# Underwater_ROV_Sensors.net
KiCad netlist of a schematic drawn in Altium Designer
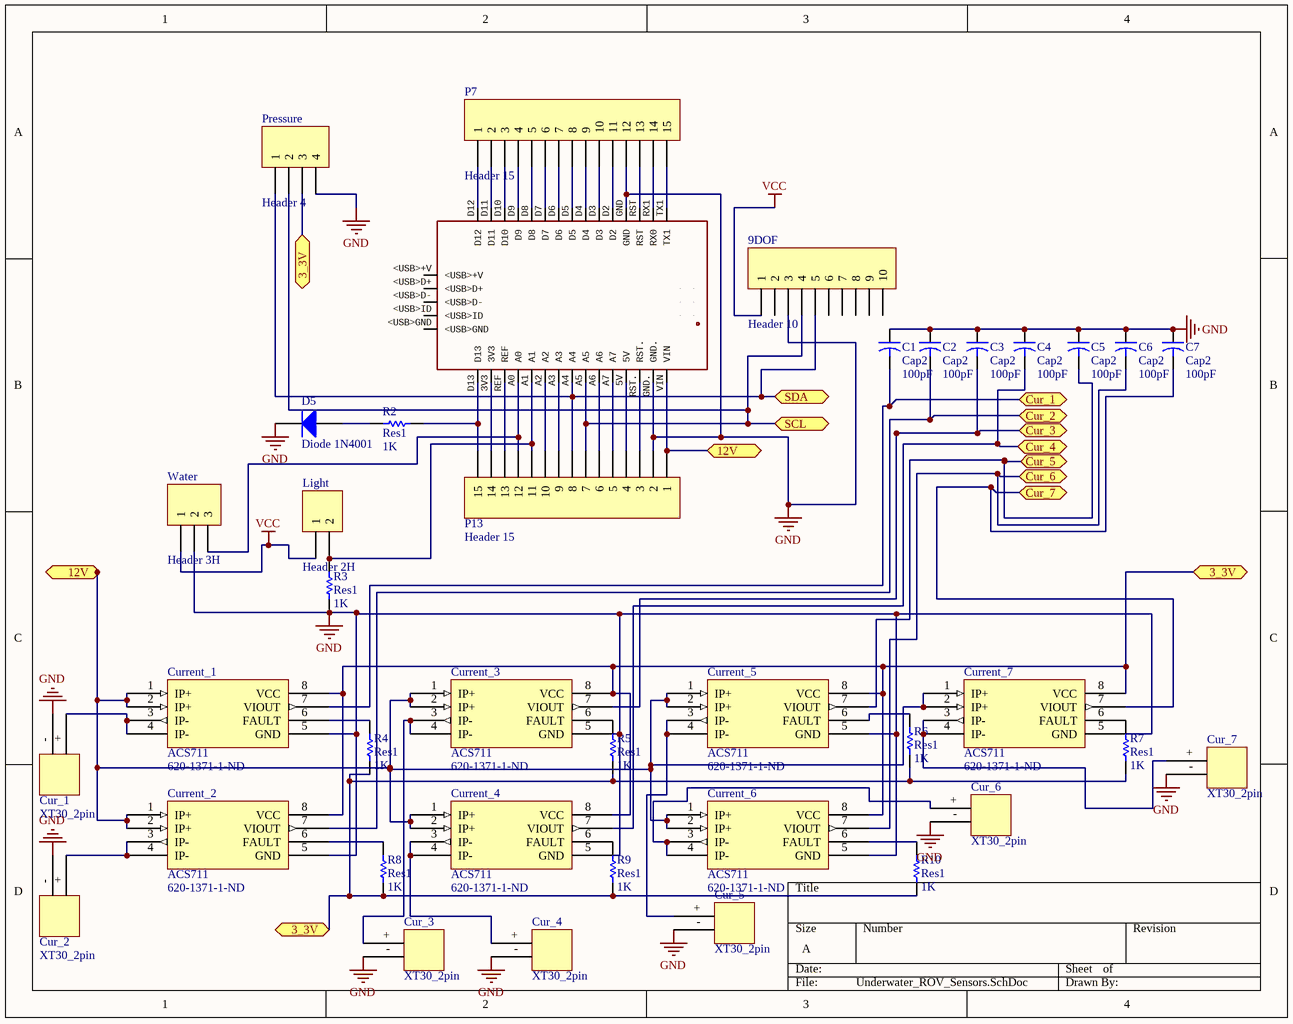
[diagram p0: Underwater_ROV_Sensors.SchDoc]

(export (version "E")
  (design (tool "Eeschema 10.0.6"))
  (components
    (comp (ref "9DOF")
      (value "Header 10")
      (footprint "HDR1X10")
      (description "Header, 10-Pin")
      (fields (field (name "PUBLISHER") "Altium Limited"))
      (libsource (lib "Miscellaneous Connectors") (part "Header 10"))
    )
    (comp (ref "C1")
      (value "Cap2")
      (footprint "CAPR5-4X5")
      (description "Capacitor")
      (fields (field (name "ALTIUM_VALUE") "100pF") (field (name "PUBLISHER") "Altium Limited"))
      (libsource (lib "Miscellaneous Devices") (part "Cap2"))
    )
    (comp (ref "C2")
      (value "Cap2")
      (footprint "CAPR5-4X5")
      (description "Capacitor")
      (fields (field (name "ALTIUM_VALUE") "100pF") (field (name "PUBLISHER") "Altium Limited"))
      (libsource (lib "Miscellaneous Devices") (part "Cap2"))
    )
    (comp (ref "C3")
      (value "Cap2")
      (footprint "CAPR5-4X5")
      (description "Capacitor")
      (fields (field (name "ALTIUM_VALUE") "100pF") (field (name "PUBLISHER") "Altium Limited"))
      (libsource (lib "Miscellaneous Devices") (part "Cap2"))
    )
    (comp (ref "C4")
      (value "Cap2")
      (footprint "CAPR5-4X5")
      (description "Capacitor")
      (fields (field (name "ALTIUM_VALUE") "100pF") (field (name "PUBLISHER") "Altium Limited"))
      (libsource (lib "Miscellaneous Devices") (part "Cap2"))
    )
    (comp (ref "C5")
      (value "Cap2")
      (footprint "CAPR5-4X5")
      (description "Capacitor")
      (fields (field (name "ALTIUM_VALUE") "100pF") (field (name "PUBLISHER") "Altium Limited"))
      (libsource (lib "Miscellaneous Devices") (part "Cap2"))
    )
    (comp (ref "C6")
      (value "Cap2")
      (footprint "CAPR5-4X5")
      (description "Capacitor")
      (fields (field (name "ALTIUM_VALUE") "100pF") (field (name "PUBLISHER") "Altium Limited"))
      (libsource (lib "Miscellaneous Devices") (part "Cap2"))
    )
    (comp (ref "C7")
      (value "Cap2")
      (footprint "CAPR5-4X5")
      (description "Capacitor")
      (fields (field (name "ALTIUM_VALUE") "100pF") (field (name "PUBLISHER") "Altium Limited"))
      (libsource (lib "Miscellaneous Devices") (part "Cap2"))
    )
    (comp (ref "Current_1")
      (value "ACS711")
      (footprint "SOIC127P600X175-8N")
      (fields
        (field (name "MANUFACTURER") "Allegro MicroSystems, LLC")
        (field (name "MANUFACTURER PART NUMBER") "ACS711ELCTR-25AB-T")
        (field (name "SUPPLIER PART NUMBER 1") "620-1371-1-ND")
      )
      (libsource (lib "UROV_Aux_Lib") (part "ACS711"))
    )
    (comp (ref "Current_2")
      (value "ACS711")
      (footprint "SOIC127P600X175-8N")
      (fields
        (field (name "MANUFACTURER") "Allegro MicroSystems, LLC")
        (field (name "MANUFACTURER PART NUMBER") "ACS711ELCTR-25AB-T")
        (field (name "SUPPLIER PART NUMBER 1") "620-1371-1-ND")
      )
      (libsource (lib "UROV_Aux_Lib") (part "ACS711"))
    )
    (comp (ref "Current_3")
      (value "ACS711")
      (footprint "SOIC127P600X175-8N")
      (fields
        (field (name "MANUFACTURER") "Allegro MicroSystems, LLC")
        (field (name "MANUFACTURER PART NUMBER") "ACS711ELCTR-25AB-T")
        (field (name "SUPPLIER PART NUMBER 1") "620-1371-1-ND")
      )
      (libsource (lib "UROV_Aux_Lib") (part "ACS711"))
    )
    (comp (ref "Current_4")
      (value "ACS711")
      (footprint "SOIC127P600X175-8N")
      (fields
        (field (name "MANUFACTURER") "Allegro MicroSystems, LLC")
        (field (name "MANUFACTURER PART NUMBER") "ACS711ELCTR-25AB-T")
        (field (name "SUPPLIER PART NUMBER 1") "620-1371-1-ND")
      )
      (libsource (lib "UROV_Aux_Lib") (part "ACS711"))
    )
    (comp (ref "Current_5")
      (value "ACS711")
      (footprint "SOIC127P600X175-8N")
      (fields
        (field (name "MANUFACTURER") "Allegro MicroSystems, LLC")
        (field (name "MANUFACTURER PART NUMBER") "ACS711ELCTR-25AB-T")
        (field (name "SUPPLIER PART NUMBER 1") "620-1371-1-ND")
      )
      (libsource (lib "UROV_Aux_Lib") (part "ACS711"))
    )
    (comp (ref "Current_6")
      (value "ACS711")
      (footprint "SOIC127P600X175-8N")
      (fields
        (field (name "MANUFACTURER") "Allegro MicroSystems, LLC")
        (field (name "MANUFACTURER PART NUMBER") "ACS711ELCTR-25AB-T")
        (field (name "SUPPLIER PART NUMBER 1") "620-1371-1-ND")
      )
      (libsource (lib "UROV_Aux_Lib") (part "ACS711"))
    )
    (comp (ref "Current_7")
      (value "ACS711")
      (footprint "SOIC127P600X175-8N")
      (fields
        (field (name "MANUFACTURER") "Allegro MicroSystems, LLC")
        (field (name "MANUFACTURER PART NUMBER") "ACS711ELCTR-25AB-T")
        (field (name "SUPPLIER PART NUMBER 1") "620-1371-1-ND")
      )
      (libsource (lib "UROV_Aux_Lib") (part "ACS711"))
    )
    (comp (ref "Cur_1")
      (value "XT30_2pin")
      (footprint "XT30_2pin")
      (libsource (lib "UROV_Aux_Lib") (part "XT30_2pin"))
    )
    (comp (ref "Cur_2")
      (value "XT30_2pin")
      (footprint "XT30_2pin")
      (libsource (lib "UROV_Aux_Lib") (part "XT30_2pin"))
    )
    (comp (ref "Cur_3") (value "XT30_2pin") (footprint "XT30_2pin") (libsource (lib "") (part "XT30_2pin_1")))
    (comp (ref "Cur_4") (value "XT30_2pin") (footprint "XT30_2pin") (libsource (lib "") (part "XT30_2pin_1")))
    (comp (ref "Cur_5") (value "XT30_2pin") (footprint "XT30_2pin") (libsource (lib "") (part "XT30_2pin_1")))
    (comp (ref "Cur_6") (value "XT30_2pin") (footprint "XT30_2pin") (libsource (lib "") (part "XT30_2pin_1")))
    (comp (ref "Cur_7") (value "XT30_2pin") (footprint "XT30_2pin") (libsource (lib "") (part "XT30_2pin_1")))
    (comp (ref "D5")
      (value "Diode 1N4001")
      (footprint "DO-41")
      (description "1 Amp General Purpose Rectifier")
      (fields (field (name "PUBLISHER") "Altium Limited"))
      (libsource (lib "Miscellaneous Devices") (part "Diode 1N4001"))
    )
    (comp (ref "Light")
      (value "Header 2H")
      (footprint "HDR1X2H")
      (description "Header, 2-Pin, Right Angle")
      (fields (field (name "PUBLISHER") "Altium Limited"))
      (libsource (lib "Miscellaneous Connectors") (part "Header 2H"))
    )
    (comp (ref "Nano_sens")
      (value "Device for representing an Arduino Nano board with a footprint in an EAGLE design. Created by Dave Young for Element14. More EAGLE documentation at: http://www.element14.com/community/community/knode/cadsoft_eagle")
      (footprint "ARDUINO_NANO")
      (libsource (lib "E14_Arduino_revC") (part "ARDUINO_NANO"))
    )
    (comp (ref "P7")
      (value "Header 15")
      (footprint "HDR1X15")
      (description "Header, 15-Pin")
      (fields (field (name "PUBLISHER") "Altium Limited"))
      (libsource (lib "") (part "Header 15_1"))
    )
    (comp (ref "P13")
      (value "Header 15")
      (footprint "HDR1X15")
      (description "Header, 15-Pin")
      (fields (field (name "PUBLISHER") "Altium Limited"))
      (libsource (lib "Miscellaneous Connectors") (part "Header 15"))
    )
    (comp (ref "Pressure")
      (value "Header 4")
      (footprint "HDR1X4")
      (description "Header, 4-Pin")
      (fields (field (name "PUBLISHER") "Altium Limited"))
      (libsource (lib "Miscellaneous Connectors") (part "Header 4"))
    )
    (comp (ref "R2")
      (value "Res1")
      (footprint "AXIAL-0.3")
      (description "Resistor")
      (fields (field (name "ALTIUM_VALUE") "1K") (field (name "PUBLISHER") "Altium Limited"))
      (libsource (lib "Miscellaneous Devices") (part "Res1"))
    )
    (comp (ref "R3")
      (value "Res1")
      (footprint "AXIAL-0.3")
      (description "Resistor")
      (fields (field (name "ALTIUM_VALUE") "1K") (field (name "PUBLISHER") "Altium Limited"))
      (libsource (lib "Miscellaneous Devices") (part "Res1"))
    )
    (comp (ref "R4")
      (value "Res1")
      (footprint "AXIAL-0.3")
      (description "Resistor")
      (fields (field (name "ALTIUM_VALUE") "1K") (field (name "PUBLISHER") "Altium Limited"))
      (libsource (lib "Miscellaneous Devices") (part "Res1"))
    )
    (comp (ref "R5")
      (value "Res1")
      (footprint "AXIAL-0.3")
      (description "Resistor")
      (fields (field (name "ALTIUM_VALUE") "1K") (field (name "PUBLISHER") "Altium Limited"))
      (libsource (lib "Miscellaneous Devices") (part "Res1"))
    )
    (comp (ref "R6")
      (value "Res1")
      (footprint "AXIAL-0.3")
      (description "Resistor")
      (fields (field (name "ALTIUM_VALUE") "1K") (field (name "PUBLISHER") "Altium Limited"))
      (libsource (lib "Miscellaneous Devices") (part "Res1"))
    )
    (comp (ref "R7")
      (value "Res1")
      (footprint "AXIAL-0.3")
      (description "Resistor")
      (fields (field (name "ALTIUM_VALUE") "1K") (field (name "PUBLISHER") "Altium Limited"))
      (libsource (lib "Miscellaneous Devices") (part "Res1"))
    )
    (comp (ref "R8")
      (value "Res1")
      (footprint "AXIAL-0.3")
      (description "Resistor")
      (fields (field (name "ALTIUM_VALUE") "1K") (field (name "PUBLISHER") "Altium Limited"))
      (libsource (lib "Miscellaneous Devices") (part "Res1"))
    )
    (comp (ref "R9")
      (value "Res1")
      (footprint "AXIAL-0.3")
      (description "Resistor")
      (fields (field (name "ALTIUM_VALUE") "1K") (field (name "PUBLISHER") "Altium Limited"))
      (libsource (lib "Miscellaneous Devices") (part "Res1"))
    )
    (comp (ref "R10")
      (value "Res1")
      (footprint "AXIAL-0.3")
      (description "Resistor")
      (fields (field (name "ALTIUM_VALUE") "1K") (field (name "PUBLISHER") "Altium Limited"))
      (libsource (lib "Miscellaneous Devices") (part "Res1"))
    )
    (comp (ref "Water")
      (value "Header 3H")
      (footprint "HDR1X3H")
      (description "Header, 3-Pin, Right Angle")
      (fields (field (name "PUBLISHER") "Altium Limited"))
      (libsource (lib "Miscellaneous Connectors") (part "Header 3H"))
    )
  )
  (nets
    (net (code "1") (name "/3_3V") (class "Default")
      (node (ref "Current_1") (pin "8") (pinfunction "VCC_8") (pintype "power_in"))
      (node (ref "Current_2") (pin "8") (pinfunction "VCC_8") (pintype "power_in"))
      (node (ref "Current_3") (pin "8") (pinfunction "VCC_8") (pintype "power_in"))
      (node (ref "Current_4") (pin "8") (pinfunction "VCC_8") (pintype "power_in"))
      (node (ref "Current_5") (pin "8") (pinfunction "VCC_8") (pintype "power_in"))
      (node (ref "Current_6") (pin "8") (pinfunction "VCC_8") (pintype "power_in"))
      (node (ref "Current_7") (pin "8") (pinfunction "VCC_8") (pintype "power_in"))
      (node (ref "Pressure") (pin "3") (pinfunction "3_3") (pintype "passive"))
      (node (ref "R10") (pin "1") (pinfunction "1_1") (pintype "passive"))
      (node (ref "R4") (pin "1") (pinfunction "1_1") (pintype "passive"))
      (node (ref "R5") (pin "1") (pinfunction "1_1") (pintype "passive"))
      (node (ref "R6") (pin "1") (pinfunction "1_1") (pintype "passive"))
      (node (ref "R7") (pin "1") (pinfunction "1_1") (pintype "passive"))
      (node (ref "R8") (pin "1") (pinfunction "1_1") (pintype "passive"))
      (node (ref "R9") (pin "1") (pinfunction "1_1") (pintype "passive"))
    )
    (net (code "2") (name "/12V") (class "Default")
      (node (ref "Current_1") (pin "1") (pinfunction "IP+_1") (pintype "input"))
      (node (ref "Current_1") (pin "2") (pinfunction "IP+_2") (pintype "input"))
      (node (ref "Current_2") (pin "1") (pinfunction "IP+_1") (pintype "input"))
      (node (ref "Current_2") (pin "2") (pinfunction "IP+_2") (pintype "input"))
      (node (ref "Current_3") (pin "1") (pinfunction "IP+_1") (pintype "input"))
      (node (ref "Current_3") (pin "2") (pinfunction "IP+_2") (pintype "input"))
      (node (ref "Current_4") (pin "1") (pinfunction "IP+_1") (pintype "input"))
      (node (ref "Current_4") (pin "2") (pinfunction "IP+_2") (pintype "input"))
      (node (ref "Current_5") (pin "1") (pinfunction "IP+_1") (pintype "input"))
      (node (ref "Current_5") (pin "2") (pinfunction "IP+_2") (pintype "input"))
      (node (ref "Current_6") (pin "1") (pinfunction "IP+_1") (pintype "input"))
      (node (ref "Current_6") (pin "2") (pinfunction "IP+_2") (pintype "input"))
      (node (ref "Current_7") (pin "1") (pinfunction "IP+_1") (pintype "input"))
      (node (ref "Current_7") (pin "2") (pinfunction "IP+_2") (pintype "input"))
      (node (ref "Nano_sens") (pin "VIN") (pinfunction "VIN_VIN") (pintype "passive"))
      (node (ref "P13") (pin "1") (pinfunction "1_1") (pintype "passive"))
    )
    (net (code "3") (name "/Cur_1") (class "Default")
      (node (ref "C1") (pin "2") (pinfunction "2_2") (pintype "passive"))
      (node (ref "Current_1") (pin "7") (pinfunction "VIOUT_7") (pintype "output"))
    )
    (net (code "4") (name "/Cur_2") (class "Default")
      (node (ref "C2") (pin "2") (pinfunction "2_2") (pintype "passive"))
      (node (ref "Current_2") (pin "7") (pinfunction "VIOUT_7") (pintype "output"))
    )
    (net (code "5") (name "/Cur_3") (class "Default")
      (node (ref "C3") (pin "2") (pinfunction "2_2") (pintype "passive"))
      (node (ref "Current_3") (pin "7") (pinfunction "VIOUT_7") (pintype "output"))
    )
    (net (code "6") (name "/Cur_4") (class "Default")
      (node (ref "C4") (pin "2") (pinfunction "2_2") (pintype "passive"))
      (node (ref "Current_4") (pin "7") (pinfunction "VIOUT_7") (pintype "output"))
    )
    (net (code "7") (name "/Cur_5") (class "Default")
      (node (ref "C5") (pin "2") (pinfunction "2_2") (pintype "passive"))
      (node (ref "Current_5") (pin "7") (pinfunction "VIOUT_7") (pintype "output"))
    )
    (net (code "8") (name "/Cur_6") (class "Default")
      (node (ref "C6") (pin "2") (pinfunction "2_2") (pintype "passive"))
      (node (ref "Current_6") (pin "7") (pinfunction "VIOUT_7") (pintype "output"))
    )
    (net (code "9") (name "/Cur_7") (class "Default")
      (node (ref "C7") (pin "2") (pinfunction "2_2") (pintype "passive"))
      (node (ref "Current_7") (pin "7") (pinfunction "VIOUT_7") (pintype "output"))
    )
    (net (code "10") (name "/SCL") (class "Default")
      (node (ref "9DOF") (pin "4") (pinfunction "4_4") (pintype "passive"))
      (node (ref "Nano_sens") (pin "A5") (pinfunction "A5_A5") (pintype "passive"))
      (node (ref "P13") (pin "7") (pinfunction "7_7") (pintype "passive"))
      (node (ref "Pressure") (pin "2") (pinfunction "2_2") (pintype "passive"))
    )
    (net (code "11") (name "/SDA") (class "Default")
      (node (ref "9DOF") (pin "5") (pinfunction "5_5") (pintype "passive"))
      (node (ref "Nano_sens") (pin "A4") (pinfunction "A4_A4") (pintype "passive"))
      (node (ref "P13") (pin "8") (pinfunction "8_8") (pintype "passive"))
      (node (ref "Pressure") (pin "1") (pinfunction "1_1") (pintype "passive"))
    )
    (net (code "12") (name "GND") (class "Default")
      (node (ref "9DOF") (pin "3") (pinfunction "3_3") (pintype "passive"))
      (node (ref "C1") (pin "1") (pinfunction "1_1") (pintype "passive"))
      (node (ref "C2") (pin "1") (pinfunction "1_1") (pintype "passive"))
      (node (ref "C3") (pin "1") (pinfunction "1_1") (pintype "passive"))
      (node (ref "C4") (pin "1") (pinfunction "1_1") (pintype "passive"))
      (node (ref "C5") (pin "1") (pinfunction "1_1") (pintype "passive"))
      (node (ref "C6") (pin "1") (pinfunction "1_1") (pintype "passive"))
      (node (ref "C7") (pin "1") (pinfunction "1_1") (pintype "passive"))
      (node (ref "Cur_1") (pin "-") (pintype "passive"))
      (node (ref "Cur_2") (pin "-") (pintype "passive"))
      (node (ref "Cur_3") (pin "-") (pintype "passive"))
      (node (ref "Cur_4") (pin "-") (pintype "passive"))
      (node (ref "Cur_5") (pin "-") (pintype "passive"))
      (node (ref "Cur_6") (pin "-") (pintype "passive"))
      (node (ref "Cur_7") (pin "-") (pintype "passive"))
      (node (ref "Current_1") (pin "5") (pinfunction "GND_5") (pintype "power_in"))
      (node (ref "Current_2") (pin "5") (pinfunction "GND_5") (pintype "power_in"))
      (node (ref "Current_3") (pin "5") (pinfunction "GND_5") (pintype "power_in"))
      (node (ref "Current_4") (pin "5") (pinfunction "GND_5") (pintype "power_in"))
      (node (ref "Current_5") (pin "5") (pinfunction "GND_5") (pintype "power_in"))
      (node (ref "Current_6") (pin "5") (pinfunction "GND_5") (pintype "power_in"))
      (node (ref "Current_7") (pin "5") (pinfunction "GND_5") (pintype "power_in"))
      (node (ref "D5") (pin "2") (pinfunction "K_2") (pintype "passive"))
      (node (ref "Nano_sens") (pin "GND") (pinfunction "GND_GND") (pintype "passive"))
      (node (ref "Nano_sens") (pin "GND.") (pinfunction "GND._GND.") (pintype "passive"))
      (node (ref "P13") (pin "2") (pinfunction "2_2") (pintype "passive"))
      (node (ref "P7") (pin "12") (pinfunction "12_12") (pintype "passive"))
      (node (ref "Pressure") (pin "4") (pinfunction "4_4") (pintype "passive"))
      (node (ref "R3") (pin "1") (pinfunction "1_1") (pintype "passive"))
      (node (ref "Water") (pin "2") (pinfunction "2_2") (pintype "passive"))
    )
    (net (code "13") (name "Net-(Cur_1-Pad+)") (class "Default")
      (node (ref "Cur_1") (pin "+") (pintype "passive"))
      (node (ref "Current_1") (pin "3") (pinfunction "IP-_3") (pintype "output"))
      (node (ref "Current_1") (pin "4") (pinfunction "IP-_4") (pintype "passive"))
    )
    (net (code "14") (name "Net-(Cur_2-Pad+)") (class "Default")
      (node (ref "Cur_2") (pin "+") (pintype "passive"))
      (node (ref "Current_2") (pin "3") (pinfunction "IP-_3") (pintype "output"))
      (node (ref "Current_2") (pin "4") (pinfunction "IP-_4") (pintype "passive"))
    )
    (net (code "15") (name "Net-(Cur_3-Pad+)") (class "Default")
      (node (ref "Cur_3") (pin "+") (pintype "passive"))
      (node (ref "Current_3") (pin "3") (pinfunction "IP-_3") (pintype "output"))
      (node (ref "Current_3") (pin "4") (pinfunction "IP-_4") (pintype "passive"))
    )
    (net (code "16") (name "Net-(Cur_4-Pad+)") (class "Default")
      (node (ref "Cur_4") (pin "+") (pintype "passive"))
      (node (ref "Current_4") (pin "3") (pinfunction "IP-_3") (pintype "output"))
      (node (ref "Current_4") (pin "4") (pinfunction "IP-_4") (pintype "passive"))
    )
    (net (code "17") (name "Net-(Cur_5-Pad+)") (class "Default")
      (node (ref "Cur_5") (pin "+") (pintype "passive"))
      (node (ref "Current_5") (pin "3") (pinfunction "IP-_3") (pintype "output"))
      (node (ref "Current_5") (pin "4") (pinfunction "IP-_4") (pintype "passive"))
    )
    (net (code "18") (name "Net-(Cur_6-Pad+)") (class "Default")
      (node (ref "Cur_6") (pin "+") (pintype "passive"))
      (node (ref "Current_6") (pin "3") (pinfunction "IP-_3") (pintype "output"))
      (node (ref "Current_6") (pin "4") (pinfunction "IP-_4") (pintype "passive"))
    )
    (net (code "19") (name "Net-(Cur_7-Pad+)") (class "Default")
      (node (ref "Cur_7") (pin "+") (pintype "passive"))
      (node (ref "Current_7") (pin "3") (pinfunction "IP-_3") (pintype "output"))
      (node (ref "Current_7") (pin "4") (pinfunction "IP-_4") (pintype "passive"))
    )
    (net (code "20") (name "Net-(Current_1-FAULT)") (class "Default")
      (node (ref "Current_1") (pin "6") (pinfunction "FAULT_6") (pintype "passive"))
      (node (ref "R4") (pin "2") (pinfunction "2_2") (pintype "passive"))
    )
    (net (code "21") (name "Net-(Current_2-FAULT)") (class "Default")
      (node (ref "Current_2") (pin "6") (pinfunction "FAULT_6") (pintype "passive"))
      (node (ref "R8") (pin "2") (pinfunction "2_2") (pintype "passive"))
    )
    (net (code "22") (name "Net-(Current_3-FAULT)") (class "Default")
      (node (ref "Current_3") (pin "6") (pinfunction "FAULT_6") (pintype "passive"))
      (node (ref "R5") (pin "2") (pinfunction "2_2") (pintype "passive"))
    )
    (net (code "23") (name "Net-(Current_4-FAULT)") (class "Default")
      (node (ref "Current_4") (pin "6") (pinfunction "FAULT_6") (pintype "passive"))
      (node (ref "R9") (pin "2") (pinfunction "2_2") (pintype "passive"))
    )
    (net (code "24") (name "Net-(Current_5-FAULT)") (class "Default")
      (node (ref "Current_5") (pin "6") (pinfunction "FAULT_6") (pintype "passive"))
      (node (ref "R6") (pin "2") (pinfunction "2_2") (pintype "passive"))
    )
    (net (code "25") (name "Net-(Current_6-FAULT)") (class "Default")
      (node (ref "Current_6") (pin "6") (pinfunction "FAULT_6") (pintype "passive"))
      (node (ref "R10") (pin "2") (pinfunction "2_2") (pintype "passive"))
    )
    (net (code "26") (name "Net-(Current_7-FAULT)") (class "Default")
      (node (ref "Current_7") (pin "6") (pinfunction "FAULT_6") (pintype "passive"))
      (node (ref "R7") (pin "2") (pinfunction "2_2") (pintype "passive"))
    )
    (net (code "27") (name "Net-(D5-A)") (class "Default")
      (node (ref "D5") (pin "1") (pinfunction "A_1") (pintype "passive"))
      (node (ref "R2") (pin "1") (pinfunction "1_1") (pintype "passive"))
    )
    (net (code "28") (name "Net-(Light-Pad2)") (class "Default")
      (node (ref "Light") (pin "2") (pinfunction "2_2") (pintype "passive"))
      (node (ref "Nano_sens") (pin "A1") (pinfunction "A1_A1") (pintype "passive"))
      (node (ref "P13") (pin "11") (pinfunction "11_11") (pintype "passive"))
      (node (ref "R3") (pin "2") (pinfunction "2_2") (pintype "passive"))
    )
    (net (code "29") (name "Net-(Nano_sens-Pad3V3)") (class "Default")
      (node (ref "Nano_sens") (pin "3V3") (pinfunction "3V3_3V3") (pintype "passive"))
      (node (ref "P13") (pin "14") (pinfunction "14_14") (pintype "passive"))
    )
    (net (code "30") (name "Net-(Nano_sens-Pad5V)") (class "Default")
      (node (ref "Nano_sens") (pin "5V") (pinfunction "5V_5V") (pintype "passive"))
      (node (ref "P13") (pin "4") (pinfunction "4_4") (pintype "passive"))
    )
    (net (code "31") (name "Net-(Nano_sens-PadA0)") (class "Default")
      (node (ref "Nano_sens") (pin "A0") (pinfunction "A0_A0") (pintype "passive"))
      (node (ref "P13") (pin "12") (pinfunction "12_12") (pintype "passive"))
      (node (ref "Water") (pin "3") (pinfunction "3_3") (pintype "passive"))
    )
    (net (code "32") (name "Net-(Nano_sens-PadA2)") (class "Default")
      (node (ref "Nano_sens") (pin "A2") (pinfunction "A2_A2") (pintype "passive"))
      (node (ref "P13") (pin "10") (pinfunction "10_10") (pintype "passive"))
    )
    (net (code "33") (name "Net-(Nano_sens-PadA3)") (class "Default")
      (node (ref "Nano_sens") (pin "A3") (pinfunction "A3_A3") (pintype "passive"))
      (node (ref "P13") (pin "9") (pinfunction "9_9") (pintype "passive"))
    )
    (net (code "34") (name "Net-(Nano_sens-PadA6)") (class "Default")
      (node (ref "Nano_sens") (pin "A6") (pinfunction "A6_A6") (pintype "passive"))
      (node (ref "P13") (pin "6") (pinfunction "6_6") (pintype "passive"))
    )
    (net (code "35") (name "Net-(Nano_sens-PadA7)") (class "Default")
      (node (ref "Nano_sens") (pin "A7") (pinfunction "A7_A7") (pintype "passive"))
      (node (ref "P13") (pin "5") (pinfunction "5_5") (pintype "passive"))
    )
    (net (code "36") (name "Net-(Nano_sens-PadD2)") (class "Default")
      (node (ref "Nano_sens") (pin "D2") (pinfunction "D2_D2") (pintype "passive"))
      (node (ref "P7") (pin "11") (pinfunction "11_11") (pintype "passive"))
    )
    (net (code "37") (name "Net-(Nano_sens-PadD3)") (class "Default")
      (node (ref "Nano_sens") (pin "D3") (pinfunction "D3_D3") (pintype "passive"))
      (node (ref "P7") (pin "10") (pinfunction "10_10") (pintype "passive"))
    )
    (net (code "38") (name "Net-(Nano_sens-PadD4)") (class "Default")
      (node (ref "Nano_sens") (pin "D4") (pinfunction "D4_D4") (pintype "passive"))
      (node (ref "P7") (pin "9") (pinfunction "9_9") (pintype "passive"))
    )
    (net (code "39") (name "Net-(Nano_sens-PadD5)") (class "Default")
      (node (ref "Nano_sens") (pin "D5") (pinfunction "D5_D5") (pintype "passive"))
      (node (ref "P7") (pin "8") (pinfunction "8_8") (pintype "passive"))
    )
    (net (code "40") (name "Net-(Nano_sens-PadD6)") (class "Default")
      (node (ref "Nano_sens") (pin "D6") (pinfunction "D6_D6") (pintype "passive"))
      (node (ref "P7") (pin "7") (pinfunction "7_7") (pintype "passive"))
    )
    (net (code "41") (name "Net-(Nano_sens-PadD7)") (class "Default")
      (node (ref "Nano_sens") (pin "D7") (pinfunction "D7_D7") (pintype "passive"))
      (node (ref "P7") (pin "6") (pinfunction "6_6") (pintype "passive"))
    )
    (net (code "42") (name "Net-(Nano_sens-PadD8)") (class "Default")
      (node (ref "Nano_sens") (pin "D8") (pinfunction "D8_D8") (pintype "passive"))
      (node (ref "P7") (pin "5") (pinfunction "5_5") (pintype "passive"))
    )
    (net (code "43") (name "Net-(Nano_sens-PadD9)") (class "Default")
      (node (ref "Nano_sens") (pin "D9") (pinfunction "D9_D9") (pintype "passive"))
      (node (ref "P7") (pin "4") (pinfunction "4_4") (pintype "passive"))
    )
    (net (code "44") (name "Net-(Nano_sens-PadD10)") (class "Default")
      (node (ref "Nano_sens") (pin "D10") (pinfunction "D10_D10") (pintype "passive"))
      (node (ref "P7") (pin "3") (pinfunction "3_3") (pintype "passive"))
    )
    (net (code "45") (name "Net-(Nano_sens-PadD11)") (class "Default")
      (node (ref "Nano_sens") (pin "D11") (pinfunction "D11_D11") (pintype "passive"))
      (node (ref "P7") (pin "2") (pinfunction "2_2") (pintype "passive"))
    )
    (net (code "46") (name "Net-(Nano_sens-PadD12)") (class "Default")
      (node (ref "Nano_sens") (pin "D12") (pinfunction "D12_D12") (pintype "passive"))
      (node (ref "P7") (pin "1") (pinfunction "1_1") (pintype "passive"))
    )
    (net (code "47") (name "Net-(Nano_sens-PadD13)") (class "Default")
      (node (ref "Nano_sens") (pin "D13") (pinfunction "D13_D13") (pintype "passive"))
      (node (ref "P13") (pin "15") (pinfunction "15_15") (pintype "passive"))
      (node (ref "R2") (pin "2") (pinfunction "2_2") (pintype "passive"))
    )
    (net (code "48") (name "Net-(Nano_sens-PadREF)") (class "Default")
      (node (ref "Nano_sens") (pin "REF") (pinfunction "REF_REF") (pintype "passive"))
      (node (ref "P13") (pin "13") (pinfunction "13_13") (pintype "passive"))
    )
    (net (code "49") (name "Net-(Nano_sens-PadRST)") (class "Default")
      (node (ref "Nano_sens") (pin "RST") (pinfunction "RST_RST") (pintype "passive"))
      (node (ref "P7") (pin "13") (pinfunction "13_13") (pintype "passive"))
    )
    (net (code "50") (name "Net-(Nano_sens-PadRST.)") (class "Default")
      (node (ref "Nano_sens") (pin "RST.") (pinfunction "RST._RST.") (pintype "passive"))
      (node (ref "P13") (pin "3") (pinfunction "3_3") (pintype "passive"))
    )
    (net (code "51") (name "Net-(Nano_sens-PadTX1)") (class "Default")
      (node (ref "Nano_sens") (pin "TX1") (pinfunction "TX1_TX1") (pintype "passive"))
      (node (ref "P7") (pin "15") (pinfunction "15_15") (pintype "passive"))
    )
    (net (code "52") (name "Net-(Nano_sens-RX0)") (class "Default")
      (node (ref "Nano_sens") (pin "RX1") (pinfunction "RX0_RX1") (pintype "passive"))
      (node (ref "P7") (pin "14") (pinfunction "14_14") (pintype "passive"))
    )
    (net (code "53") (name "VCC") (class "Default")
      (node (ref "9DOF") (pin "1") (pinfunction "1_1") (pintype "passive"))
      (node (ref "Light") (pin "1") (pinfunction "1_1") (pintype "passive"))
      (node (ref "Water") (pin "1") (pinfunction "1_1") (pintype "passive"))
    )
    (net (code "54") (name "unconnected-(9DOF-Pad2)") (class "Default")
      (node (ref "9DOF") (pin "2") (pinfunction "2_2") (pintype "passive"))
    )
    (net (code "55") (name "unconnected-(9DOF-Pad6)") (class "Default")
      (node (ref "9DOF") (pin "6") (pinfunction "6_6") (pintype "passive"))
    )
    (net (code "56") (name "unconnected-(9DOF-Pad7)") (class "Default")
      (node (ref "9DOF") (pin "7") (pinfunction "7_7") (pintype "passive"))
    )
    (net (code "57") (name "unconnected-(9DOF-Pad8)") (class "Default")
      (node (ref "9DOF") (pin "8") (pinfunction "8_8") (pintype "passive"))
    )
    (net (code "58") (name "unconnected-(9DOF-Pad9)") (class "Default")
      (node (ref "9DOF") (pin "9") (pinfunction "9_9") (pintype "passive"))
    )
    (net (code "59") (name "unconnected-(9DOF-Pad10)") (class "Default")
      (node (ref "9DOF") (pin "10") (pinfunction "10_10") (pintype "passive"))
    )
    (net (code "60") (name "unconnected-(Nano_sens-Pad5V.)") (class "Default")
      (node (ref "Nano_sens") (pin "5V.") (pinfunction "5V._5V.") (pintype "passive"))
    )
    (net (code "61") (name "unconnected-(Nano_sens-Pad<USB>+V)") (class "Default")
      (node (ref "Nano_sens") (pin "<USB>+V") (pinfunction "<USB>+V_<USB>+V") (pintype "passive"))
    )
    (net (code "62") (name "unconnected-(Nano_sens-Pad<USB>D+)") (class "Default")
      (node (ref "Nano_sens") (pin "<USB>D+") (pinfunction "<USB>D+_<USB>D+") (pintype "passive"))
    )
    (net (code "63") (name "unconnected-(Nano_sens-Pad<USB>D-)") (class "Default")
      (node (ref "Nano_sens") (pin "<USB>D-") (pinfunction "<USB>D-_<USB>D-") (pintype "passive"))
    )
    (net (code "64") (name "unconnected-(Nano_sens-Pad<USB>GND)") (class "Default")
      (node (ref "Nano_sens") (pin "<USB>GND") (pinfunction "<USB>GND_<USB>GND") (pintype "passive"))
    )
    (net (code "65") (name "unconnected-(Nano_sens-Pad<USB>ID)") (class "Default")
      (node (ref "Nano_sens") (pin "<USB>ID") (pinfunction "<USB>ID_<USB>ID") (pintype "passive"))
    )
    (net (code "66") (name "unconnected-(Nano_sens-PadGND_)") (class "Default")
      (node (ref "Nano_sens") (pin "GND_") (pinfunction "GND__GND_") (pintype "passive"))
    )
    (net (code "67") (name "unconnected-(Nano_sens-PadMISO)") (class "Default")
      (node (ref "Nano_sens") (pin "MISO") (pinfunction "MISO_MISO") (pintype "passive"))
    )
    (net (code "68") (name "unconnected-(Nano_sens-PadMOSI)") (class "Default")
      (node (ref "Nano_sens") (pin "MOSI") (pinfunction "MOSI_MOSI") (pintype "passive"))
    )
    (net (code "69") (name "unconnected-(Nano_sens-PadRESET..)") (class "Default")
      (node (ref "Nano_sens") (pin "RESET..") (pinfunction "RESET.._RESET..") (pintype "passive"))
    )
    (net (code "70") (name "unconnected-(Nano_sens-PadSCK)") (class "Default")
      (node (ref "Nano_sens") (pin "SCK") (pinfunction "SCK_SCK") (pintype "passive"))
    )
  )
)
